# Sensor.net
KiCad netlist of a schematic drawn in Altium Designer
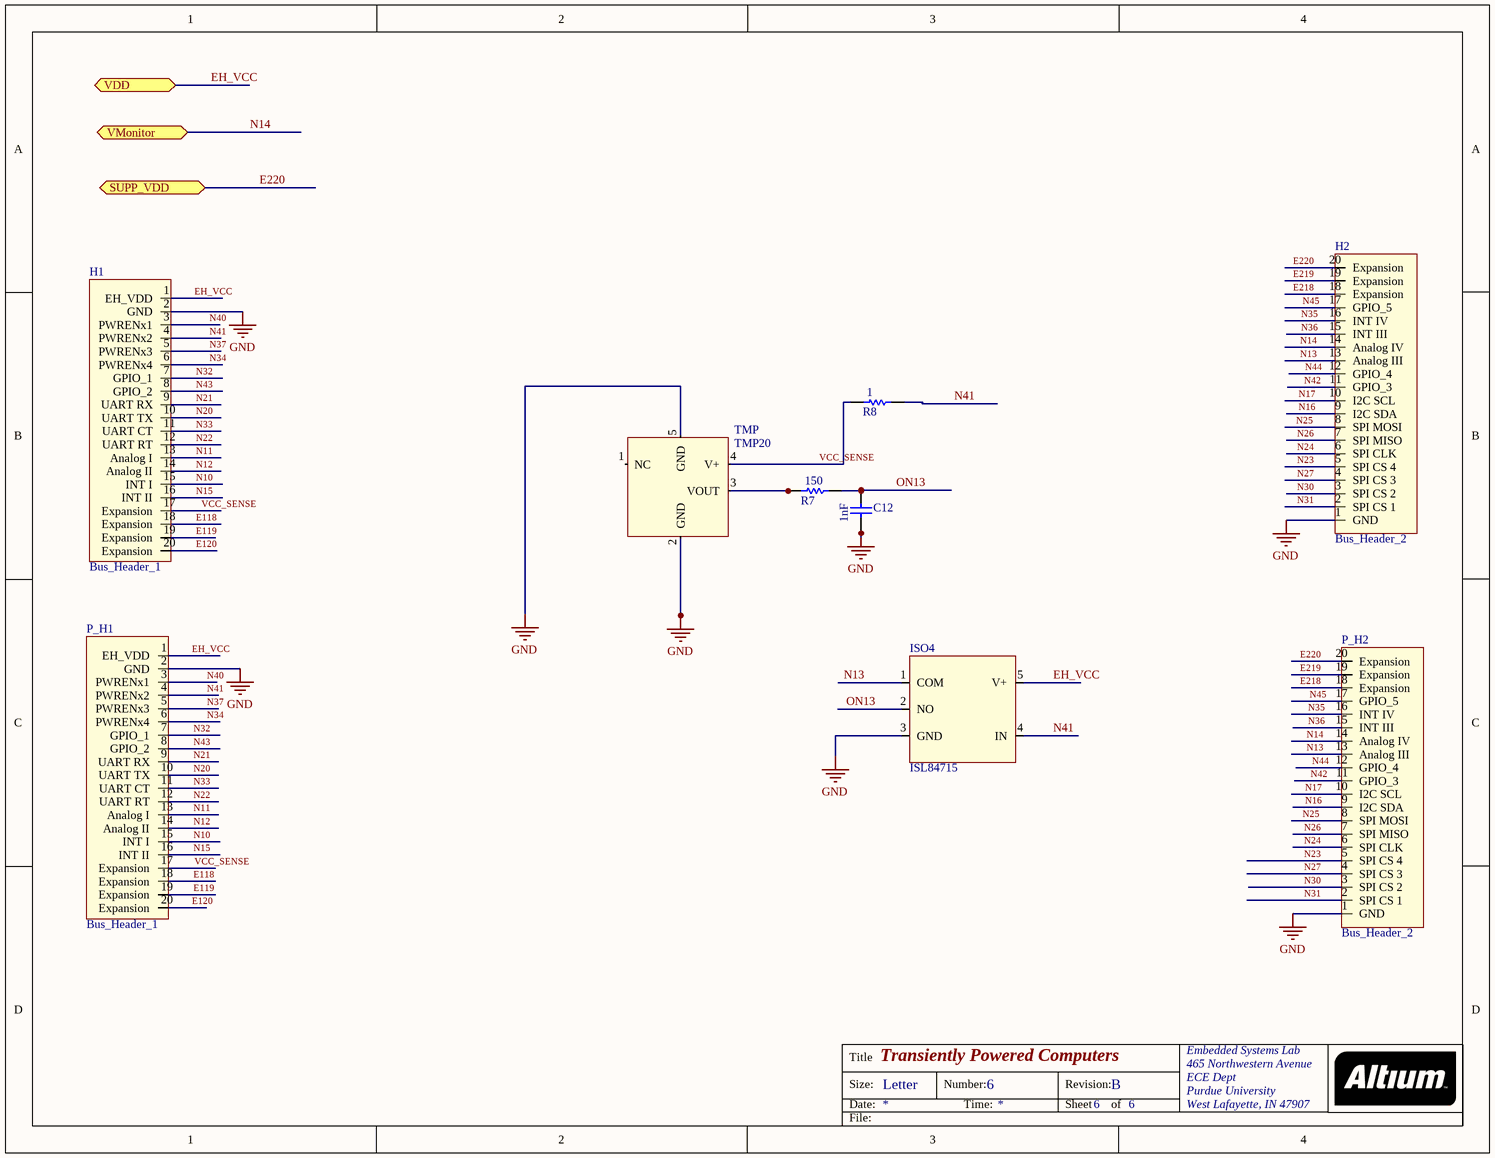
[diagram p0: Sensor.SchDoc]

(export (version "E")
  (design (tool "Eeschema 10.0.6"))
  (components
    (comp (ref "C12")
      (value "1nF")
      (footprint "CAPC0402(1005)60_N")
      (description "CAP 1uF 4V ±10% 0402 (1005 Metric) Thickness 0.6mm SMD")
      (fields (field (name "TOLERANCE") "±10%") (field (name "Comment") "CAP 1uF 4V 0402(1005)"))
      (libsource (lib "Altium Content Vault") (part "CMP-1034-02111-1"))
    )
    (comp (ref "H1")
      (value "Bus_Header_1")
      (footprint "Male Single row 20 pin header")
      (libsource (lib "") (part "Bus_Header_1_1"))
    )
    (comp (ref "H2")
      (value "Bus_Header_2")
      (footprint "Male Single row 20 pin header")
      (libsource (lib "Basic_components_hrishi") (part "Bus_Header_2"))
    )
    (comp (ref "ISO4")
      (value "ISL84715")
      (footprint "ISL84715")
      (libsource (lib "Basic_components_hrishi") (part "ISL84715"))
    )
    (comp (ref "P_H1")
      (value "Bus_Header_1")
      (footprint "SMT 20 -pin single row female header")
      (libsource (lib "Basic_components_hrishi") (part "Bus_Header_1"))
    )
    (comp (ref "P_H2")
      (value "Bus_Header_2")
      (footprint "SMT 20 -pin single row female header")
      (libsource (lib "Basic_components_hrishi") (part "Bus_Header_2"))
    )
    (comp (ref "R7")
      (value "150")
      (footprint "RESC0805(2012)_M")
      (description "3R3 0.125W 5% 0805 (2012 Metric)  SMD")
      (fields (field (name "TOLERANCE") "5 %") (field (name "POWER") "0.125 W"))
      (libsource (lib "Altium Content Vault") (part "CMP-1013-00014-1"))
    )
    (comp (ref "R8")
      (value "1")
      (footprint "RESC0805(2012)_M")
      (description "3R3 0.125W 5% 0805 (2012 Metric)  SMD")
      (fields (field (name "TOLERANCE") "5 %") (field (name "POWER") "0.125 W"))
      (libsource (lib "Altium Content Vault") (part "CMP-1013-00014-1"))
    )
    (comp (ref "TMP")
      (value "TMP20")
      (footprint "TMP20")
      (libsource (lib "Basic_components_hrishi") (part "TMP20"))
    )
  )
  (nets
    (net (code "1") (name "/E118") (class "Default")
      (node (ref "H1") (pin "18") (pinfunction "Expansion_18") (pintype "passive"))
      (node (ref "P_H1") (pin "18") (pinfunction "Expansion_18") (pintype "passive"))
    )
    (net (code "2") (name "/E119") (class "Default")
      (node (ref "H1") (pin "19") (pinfunction "Expansion_19") (pintype "passive"))
      (node (ref "P_H1") (pin "19") (pinfunction "Expansion_19") (pintype "passive"))
    )
    (net (code "3") (name "/E120") (class "Default")
      (node (ref "H1") (pin "20") (pinfunction "Expansion_20") (pintype "passive"))
      (node (ref "P_H1") (pin "20") (pinfunction "Expansion_20") (pintype "passive"))
    )
    (net (code "4") (name "/E218") (class "Default")
      (node (ref "H2") (pin "18") (pinfunction "Expansion_18") (pintype "passive"))
      (node (ref "P_H2") (pin "18") (pinfunction "Expansion_18") (pintype "passive"))
    )
    (net (code "5") (name "/E219") (class "Default")
      (node (ref "H2") (pin "19") (pinfunction "Expansion_19") (pintype "passive"))
      (node (ref "P_H2") (pin "19") (pinfunction "Expansion_19") (pintype "passive"))
    )
    (net (code "6") (name "/E220") (class "Default")
      (node (ref "H2") (pin "20") (pinfunction "Expansion_20") (pintype "passive"))
      (node (ref "P_H2") (pin "20") (pinfunction "Expansion_20") (pintype "passive"))
    )
    (net (code "7") (name "/EH_VCC") (class "Default")
      (node (ref "H1") (pin "1") (pinfunction "EH_VDD_1") (pintype "passive"))
      (node (ref "ISO4") (pin "5") (pinfunction "V+_5") (pintype "passive"))
      (node (ref "P_H1") (pin "1") (pinfunction "EH_VDD_1") (pintype "passive"))
    )
    (net (code "8") (name "/N10") (class "Default")
      (node (ref "H1") (pin "15") (pinfunction "INT_I_15") (pintype "passive"))
      (node (ref "P_H1") (pin "15") (pinfunction "INT_I_15") (pintype "passive"))
    )
    (net (code "9") (name "/N11") (class "Default")
      (node (ref "H1") (pin "13") (pinfunction "Analog_I_13") (pintype "passive"))
      (node (ref "P_H1") (pin "13") (pinfunction "Analog_I_13") (pintype "passive"))
    )
    (net (code "10") (name "/N12") (class "Default")
      (node (ref "H1") (pin "14") (pinfunction "Analog_II_14") (pintype "passive"))
      (node (ref "P_H1") (pin "14") (pinfunction "Analog_II_14") (pintype "passive"))
    )
    (net (code "11") (name "/N13") (class "Default")
      (node (ref "H2") (pin "13") (pinfunction "Analog_III_13") (pintype "passive"))
      (node (ref "ISO4") (pin "1") (pinfunction "COM_1") (pintype "passive"))
      (node (ref "P_H2") (pin "13") (pinfunction "Analog_III_13") (pintype "passive"))
    )
    (net (code "12") (name "/N14") (class "Default")
      (node (ref "H2") (pin "14") (pinfunction "Analog_IV_14") (pintype "passive"))
      (node (ref "P_H2") (pin "14") (pinfunction "Analog_IV_14") (pintype "passive"))
    )
    (net (code "13") (name "/N15") (class "Default")
      (node (ref "H1") (pin "16") (pinfunction "INT_II_16") (pintype "passive"))
      (node (ref "P_H1") (pin "16") (pinfunction "INT_II_16") (pintype "passive"))
    )
    (net (code "14") (name "/N16") (class "Default")
      (node (ref "H2") (pin "9") (pinfunction "I2C_SDA_9") (pintype "passive"))
      (node (ref "P_H2") (pin "9") (pinfunction "I2C_SDA_9") (pintype "passive"))
    )
    (net (code "15") (name "/N17") (class "Default")
      (node (ref "H2") (pin "10") (pinfunction "I2C_SCL_10") (pintype "passive"))
      (node (ref "P_H2") (pin "10") (pinfunction "I2C_SCL_10") (pintype "passive"))
    )
    (net (code "16") (name "/N20") (class "Default")
      (node (ref "H1") (pin "10") (pinfunction "UART_TX_10") (pintype "passive"))
      (node (ref "P_H1") (pin "10") (pinfunction "UART_TX_10") (pintype "passive"))
    )
    (net (code "17") (name "/N21") (class "Default")
      (node (ref "H1") (pin "9") (pinfunction "UART_RX_9") (pintype "passive"))
      (node (ref "P_H1") (pin "9") (pinfunction "UART_RX_9") (pintype "passive"))
    )
    (net (code "18") (name "/N22") (class "Default")
      (node (ref "H1") (pin "12") (pinfunction "UART_RT_12") (pintype "passive"))
      (node (ref "P_H1") (pin "12") (pinfunction "UART_RT_12") (pintype "passive"))
    )
    (net (code "19") (name "/N23") (class "Default")
      (node (ref "H2") (pin "5") (pinfunction "SPI_CS_4_5") (pintype "passive"))
      (node (ref "P_H2") (pin "5") (pinfunction "SPI_CS_4_5") (pintype "passive"))
    )
    (net (code "20") (name "/N24") (class "Default")
      (node (ref "H2") (pin "6") (pinfunction "SPI_CLK_6") (pintype "passive"))
      (node (ref "P_H2") (pin "6") (pinfunction "SPI_CLK_6") (pintype "passive"))
    )
    (net (code "21") (name "/N25") (class "Default")
      (node (ref "H2") (pin "8") (pinfunction "SPI_MOSI_8") (pintype "passive"))
      (node (ref "P_H2") (pin "8") (pinfunction "SPI_MOSI_8") (pintype "passive"))
    )
    (net (code "22") (name "/N26") (class "Default")
      (node (ref "H2") (pin "7") (pinfunction "SPI_MISO_7") (pintype "passive"))
      (node (ref "P_H2") (pin "7") (pinfunction "SPI_MISO_7") (pintype "passive"))
    )
    (net (code "23") (name "/N27") (class "Default")
      (node (ref "H2") (pin "4") (pinfunction "SPI_CS_3_4") (pintype "passive"))
      (node (ref "P_H2") (pin "4") (pinfunction "SPI_CS_3_4") (pintype "passive"))
    )
    (net (code "24") (name "/N30") (class "Default")
      (node (ref "H2") (pin "3") (pinfunction "SPI_CS_2_3") (pintype "passive"))
      (node (ref "P_H2") (pin "3") (pinfunction "SPI_CS_2_3") (pintype "passive"))
    )
    (net (code "25") (name "/N31") (class "Default")
      (node (ref "H2") (pin "2") (pinfunction "SPI_CS_1_2") (pintype "passive"))
      (node (ref "P_H2") (pin "2") (pinfunction "SPI_CS_1_2") (pintype "passive"))
    )
    (net (code "26") (name "/N32") (class "Default")
      (node (ref "H1") (pin "7") (pinfunction "GPIO_1_7") (pintype "passive"))
      (node (ref "P_H1") (pin "7") (pinfunction "GPIO_1_7") (pintype "passive"))
    )
    (net (code "27") (name "/N33") (class "Default")
      (node (ref "H1") (pin "11") (pinfunction "UART_CT_11") (pintype "passive"))
      (node (ref "P_H1") (pin "11") (pinfunction "UART_CT_11") (pintype "passive"))
    )
    (net (code "28") (name "/N34") (class "Default")
      (node (ref "H1") (pin "6") (pinfunction "PWRENx4_6") (pintype "passive"))
      (node (ref "P_H1") (pin "6") (pinfunction "PWRENx4_6") (pintype "passive"))
    )
    (net (code "29") (name "/N35") (class "Default")
      (node (ref "H2") (pin "16") (pinfunction "INT_IV_16") (pintype "passive"))
      (node (ref "P_H2") (pin "16") (pinfunction "INT_IV_16") (pintype "passive"))
    )
    (net (code "30") (name "/N36") (class "Default")
      (node (ref "H2") (pin "15") (pinfunction "INT_III_15") (pintype "passive"))
      (node (ref "P_H2") (pin "15") (pinfunction "INT_III_15") (pintype "passive"))
    )
    (net (code "31") (name "/N37") (class "Default")
      (node (ref "H1") (pin "5") (pinfunction "PWRENx3_5") (pintype "passive"))
      (node (ref "P_H1") (pin "5") (pinfunction "PWRENx3_5") (pintype "passive"))
    )
    (net (code "32") (name "/N40") (class "Default")
      (node (ref "H1") (pin "3") (pinfunction "PWRENx1_3") (pintype "passive"))
      (node (ref "P_H1") (pin "3") (pinfunction "PWRENx1_3") (pintype "passive"))
    )
    (net (code "33") (name "/N41") (class "Default")
      (node (ref "H1") (pin "4") (pinfunction "PWRENx2_4") (pintype "passive"))
      (node (ref "ISO4") (pin "4") (pinfunction "IN_4") (pintype "passive"))
      (node (ref "P_H1") (pin "4") (pinfunction "PWRENx2_4") (pintype "passive"))
      (node (ref "R8") (pin "1") (pinfunction "1_1") (pintype "passive"))
    )
    (net (code "34") (name "/N42") (class "Default")
      (node (ref "H2") (pin "11") (pinfunction "GPIO_3_11") (pintype "passive"))
      (node (ref "P_H2") (pin "11") (pinfunction "GPIO_3_11") (pintype "passive"))
    )
    (net (code "35") (name "/N43") (class "Default")
      (node (ref "H1") (pin "8") (pinfunction "GPIO_2_8") (pintype "passive"))
      (node (ref "P_H1") (pin "8") (pinfunction "GPIO_2_8") (pintype "passive"))
    )
    (net (code "36") (name "/N44") (class "Default")
      (node (ref "H2") (pin "12") (pinfunction "GPIO_4_12") (pintype "passive"))
      (node (ref "P_H2") (pin "12") (pinfunction "GPIO_4_12") (pintype "passive"))
    )
    (net (code "37") (name "/N45") (class "Default")
      (node (ref "H2") (pin "17") (pinfunction "GPIO_5_17") (pintype "passive"))
      (node (ref "P_H2") (pin "17") (pinfunction "GPIO_5_17") (pintype "passive"))
    )
    (net (code "38") (name "/ON13") (class "Default")
      (node (ref "C12") (pin "2") (pinfunction "2_2") (pintype "passive"))
      (node (ref "ISO4") (pin "2") (pinfunction "NO_2") (pintype "passive"))
      (node (ref "R7") (pin "1") (pinfunction "1_1") (pintype "passive"))
    )
    (net (code "39") (name "/VCC_SENSE") (class "Default")
      (node (ref "H1") (pin "17") (pinfunction "Expansion_17") (pintype "passive"))
      (node (ref "P_H1") (pin "17") (pinfunction "Expansion_17") (pintype "passive"))
      (node (ref "R8") (pin "2") (pinfunction "2_2") (pintype "passive"))
      (node (ref "TMP") (pin "4") (pinfunction "V+_4") (pintype "passive"))
    )
    (net (code "40") (name "GND") (class "Default")
      (node (ref "C12") (pin "1") (pinfunction "1_1") (pintype "passive"))
      (node (ref "H1") (pin "2") (pinfunction "GND_2") (pintype "passive"))
      (node (ref "H2") (pin "1") (pinfunction "GND_1") (pintype "passive"))
      (node (ref "ISO4") (pin "3") (pinfunction "GND_3") (pintype "passive"))
      (node (ref "P_H1") (pin "2") (pinfunction "GND_2") (pintype "passive"))
      (node (ref "P_H2") (pin "1") (pinfunction "GND_1") (pintype "passive"))
      (node (ref "TMP") (pin "2") (pinfunction "GND_2") (pintype "passive"))
      (node (ref "TMP") (pin "5") (pinfunction "GND_5") (pintype "passive"))
    )
    (net (code "41") (name "Net-(TMP-VOUT)") (class "Default")
      (node (ref "R7") (pin "2") (pinfunction "2_2") (pintype "passive"))
      (node (ref "TMP") (pin "3") (pinfunction "VOUT_3") (pintype "passive"))
    )
    (net (code "42") (name "unconnected-(TMP-NC-Pad1)") (class "Default")
      (node (ref "TMP") (pin "1") (pinfunction "NC_1") (pintype "passive"))
    )
  )
)
